# USB.net
KiCad netlist of a schematic drawn in Altium Designer
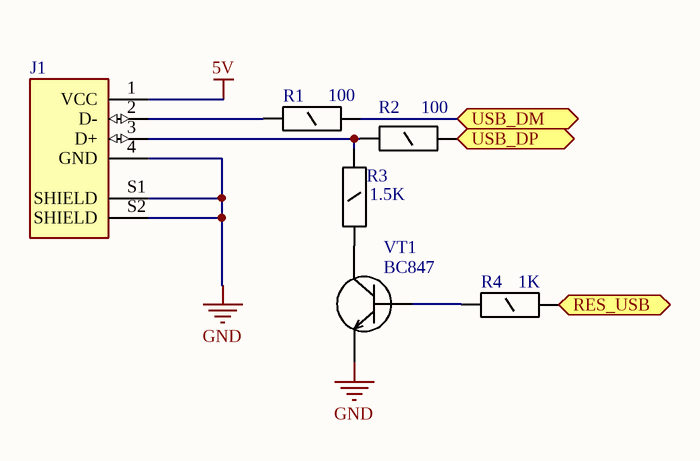
[diagram p0: USB.SchDoc]

(export (version "E")
  (design (tool "Eeschema 10.0.6"))
  (components
    (comp (ref "J1")
      (value "USBB")
      (footprint "SAMTEC_USB-B-S-X-X-TH")
      (description "USB-B (USB TYPE-B) USB 2.0 Receptacle Connector 4 Position Through Hole, Right Angle")
      (fields (field (name "MF") "Samtec"))
      (libsource (lib "USB-B-S-X-X-TH") (part "USB-B-S-X-X-TH"))
    )
    (comp (ref "R1")
      (value "100")
      (footprint "R_1206")
      (description "0,25 Вт")
      (fields (field (name "POWER") "0.25 Вт") (field (name "TOLERANCE") "5%"))
      (libsource (lib "") (part "Резистор 1206_1"))
    )
    (comp (ref "R2")
      (value "100")
      (footprint "R_1206")
      (description "0,25 Вт")
      (fields (field (name "POWER") "0.25 Вт") (field (name "TOLERANCE") "5%"))
      (libsource (lib "") (part "Резистор 1206_1"))
    )
    (comp (ref "R3")
      (value "1.5K")
      (footprint "R_1206")
      (description "0,25 Вт")
      (fields (field (name "POWER") "0.25 Вт") (field (name "TOLERANCE") "5%"))
      (libsource (lib "Res_end_Cap") (part "Резистор 1206"))
    )
    (comp (ref "R4")
      (value "1K")
      (footprint "R_1206")
      (description "0,25 Вт")
      (fields (field (name "POWER") "0.25 Вт") (field (name "TOLERANCE") "5%"))
      (libsource (lib "") (part "Резистор 1206_1"))
    )
    (comp (ref "VT1")
      (value "BC847")
      (footprint "SOT23")
      (description "NPN, SMD")
      (libsource (lib "Диоды и транзисторы") (part "BC847"))
    )
  )
  (nets
    (net (code "1") (name "/RES_USB") (class "Default")
      (node (ref "R4") (pin "1") (pinfunction "1_1") (pintype "passive"))
    )
    (net (code "2") (name "/USB_DM") (class "Default")
      (node (ref "R1") (pin "1") (pinfunction "1_1") (pintype "passive"))
    )
    (net (code "3") (name "/USB_DP") (class "Default")
      (node (ref "R2") (pin "1") (pinfunction "1_1") (pintype "passive"))
    )
    (net (code "4") (name "5V") (class "Default")
      (node (ref "J1") (pin "1") (pinfunction "VCC_1") (pintype "power_in"))
    )
    (net (code "5") (name "GND") (class "Default")
      (node (ref "J1") (pin "4") (pinfunction "GND_4") (pintype "power_in"))
      (node (ref "J1") (pin "S1") (pinfunction "SHIELD_S1") (pintype "passive"))
      (node (ref "J1") (pin "S2") (pinfunction "SHIELD_S2") (pintype "passive"))
      (node (ref "VT1") (pin "2") (pinfunction "E_2") (pintype "passive"))
    )
    (net (code "6") (name "Net-(J1-D+)") (class "Default")
      (node (ref "J1") (pin "3") (pinfunction "D+_3") (pintype "bidirectional"))
      (node (ref "R2") (pin "2") (pinfunction "2_2") (pintype "passive"))
      (node (ref "R3") (pin "1") (pinfunction "1_1") (pintype "passive"))
    )
    (net (code "7") (name "Net-(J1-D-)") (class "Default")
      (node (ref "J1") (pin "2") (pinfunction "D-_2") (pintype "bidirectional"))
      (node (ref "R1") (pin "2") (pinfunction "2_2") (pintype "passive"))
    )
    (net (code "8") (name "Net-(VT1-B)") (class "Default")
      (node (ref "R4") (pin "2") (pinfunction "2_2") (pintype "passive"))
      (node (ref "VT1") (pin "1") (pinfunction "B_1") (pintype "passive"))
    )
    (net (code "9") (name "Net-(VT1-K)") (class "Default")
      (node (ref "R3") (pin "2") (pinfunction "2_2") (pintype "passive"))
      (node (ref "VT1") (pin "3") (pinfunction "K_3") (pintype "passive"))
    )
  )
)
